# -LTC3405A.net
KiCad netlist of a schematic drawn in Altium Designer
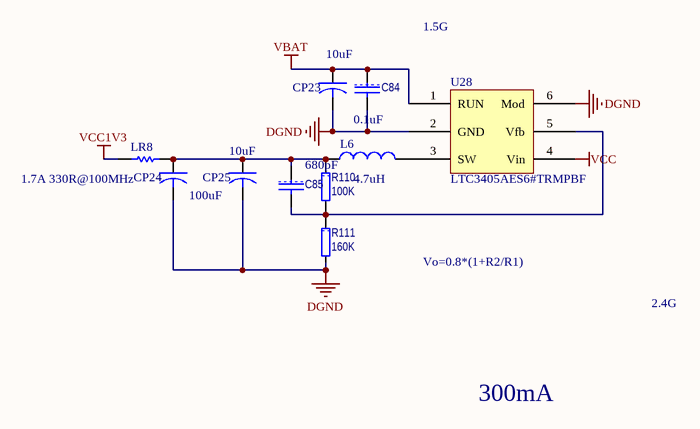
[diagram p0: -LTC3405A_电源.SchDoc]

(export (version "E")
  (design (tool "Eeschema 10.0.6"))
  (components
    (comp (ref "C84")
      (value "0.1uF")
      (footprint "1608[0603]")
      (description "多层陶瓷电容器MLCC - SMD/SMT 0603 0.1uF 50volts X7R 10%")
      (fields (field (name "MANUFACTURER") "TDK") (field (name "MANUFACTURER PART NUMBER") "C1608X7R1H104K"))
      (libsource (lib "*") (part "CAP"))
    )
    (comp (ref "C85")
      (value "680pF")
      (footprint "1608[0603]")
      (description "多层陶瓷电容器MLCC - SMD/SMT 0603 50volts 680pF X7R 10%")
      (fields (field (name "MANUFACTURER") "TDK") (field (name "MANUFACTURER PART NUMBER") "C1608X7R1H681K"))
      (libsource (lib "*") (part "CAP"))
    )
    (comp (ref "CP23")
      (value "10uF")
      (footprint "3216[1206]")
      (description "钽质电容器-固体SMD 16volts 10uF 10%")
      (fields (field (name "MANUFACTURER") "AVX") (field (name "MANUFACTURER PART NUMBER") "TAJA106K016RNJ"))
      (libsource (lib "*") (part "CAPACITOR"))
    )
    (comp (ref "CP24")
      (value "100uF")
      (footprint "6032")
      (description "钽质电容器-固体SMD 16V 100uF 10%")
      (fields (field (name "MANUFACTURER") "AVX") (field (name "MANUFACTURER PART NUMBER") "TAJC107K016RNJ"))
      (libsource (lib "*") (part "CAPACITOR"))
    )
    (comp (ref "CP25")
      (value "10uF")
      (footprint "3216[1206]")
      (description "钽质电容器-固体SMD 16volts 10uF 10%")
      (fields (field (name "MANUFACTURER") "AVX") (field (name "MANUFACTURER PART NUMBER") "TAJA106K016RNJ"))
      (libsource (lib "*") (part "CAPACITOR"))
    )
    (comp (ref "L6")
      (value "4.7uH")
      (footprint "INDP3232")
      (description "Inductor")
      (fields (field (name "Comment") "CDRH2D18/HP 2R2") (field (name "PUBLISHER") "Altium Limited"))
      (libsource (lib "Miscellaneous Devices") (part "Inductor"))
    )
    (comp (ref "LR8")
      (value "1.7A 330R@100MHz")
      (footprint "0603RV")
      (description "Semiconductor Resistor")
      (fields (field (name "Comment") "MPZ1608S331A") (field (name "PUBLISHER") "Altium Limited"))
      (libsource (lib "Miscellaneous Devices") (part "Res Semi"))
    )
    (comp (ref "R110")
      (value "100K")
      (footprint "0603R")
      (description "RES")
      (fields (field (name "MANUFACTURER") "vishay"))
      (libsource (lib "*") (part "RES"))
    )
    (comp (ref "R111")
      (value "160K")
      (footprint "0603R")
      (description "RES")
      (fields (field (name "MANUFACTURER") "vishay"))
      (libsource (lib "*") (part "RES"))
    )
    (comp (ref "U28")
      (value "LTC3405AES6#TRMPBF")
      (footprint "SOT26A-6N")
      (description "IC REG BUCK SYNC ADJ .3A SOT23-6")
      (fields (field (name "MANUFACTURER") "Linear Technology"))
      (libsource (lib "S3C2440V9") (part "LTC3405A"))
    )
  )
  (nets
    (net (code "1") (name "DGND") (class "Default")
      (node (ref "C84") (pin "2") (pinfunction "2_2") (pintype "passive"))
      (node (ref "CP23") (pin "2") (pinfunction "2_2") (pintype "passive"))
      (node (ref "CP24") (pin "2") (pinfunction "2_2") (pintype "passive"))
      (node (ref "CP25") (pin "2") (pinfunction "2_2") (pintype "passive"))
      (node (ref "R111") (pin "2") (pinfunction "2_2") (pintype "passive"))
      (node (ref "U28") (pin "2") (pinfunction "GND_2") (pintype "passive"))
      (node (ref "U28") (pin "6") (pinfunction "Mod_6") (pintype "passive"))
    )
    (net (code "2") (name "Net-(C85-Pad1)") (class "Default")
      (node (ref "C85") (pin "1") (pinfunction "1_1") (pintype "passive"))
      (node (ref "CP24") (pin "1") (pinfunction "1_1") (pintype "passive"))
      (node (ref "CP25") (pin "1") (pinfunction "1_1") (pintype "passive"))
      (node (ref "L6") (pin "1") (pinfunction "1_1") (pintype "passive"))
      (node (ref "LR8") (pin "1") (pinfunction "1_1") (pintype "passive"))
      (node (ref "R110") (pin "1") (pinfunction "1_1") (pintype "passive"))
    )
    (net (code "3") (name "Net-(U28-SW)") (class "Default")
      (node (ref "L6") (pin "2") (pinfunction "2_2") (pintype "passive"))
      (node (ref "U28") (pin "3") (pinfunction "SW_3") (pintype "passive"))
    )
    (net (code "4") (name "Net-(U28-Vfb)") (class "Default")
      (node (ref "C85") (pin "2") (pinfunction "2_2") (pintype "passive"))
      (node (ref "R110") (pin "2") (pinfunction "2_2") (pintype "passive"))
      (node (ref "R111") (pin "1") (pinfunction "1_1") (pintype "passive"))
      (node (ref "U28") (pin "5") (pinfunction "Vfb_5") (pintype "passive"))
    )
    (net (code "5") (name "VBAT") (class "Default")
      (node (ref "C84") (pin "1") (pinfunction "1_1") (pintype "passive"))
      (node (ref "CP23") (pin "1") (pinfunction "1_1") (pintype "passive"))
      (node (ref "U28") (pin "1") (pinfunction "RUN_1") (pintype "passive"))
    )
    (net (code "6") (name "VCC") (class "Default")
      (node (ref "U28") (pin "4") (pinfunction "Vin_4") (pintype "passive"))
    )
    (net (code "7") (name "VCC1V3") (class "Default")
      (node (ref "LR8") (pin "2") (pinfunction "2_2") (pintype "passive"))
    )
  )
)
